# Sensor_IMU_MPU-6000_SPI.net
KiCad netlist of a schematic drawn in EAGLE
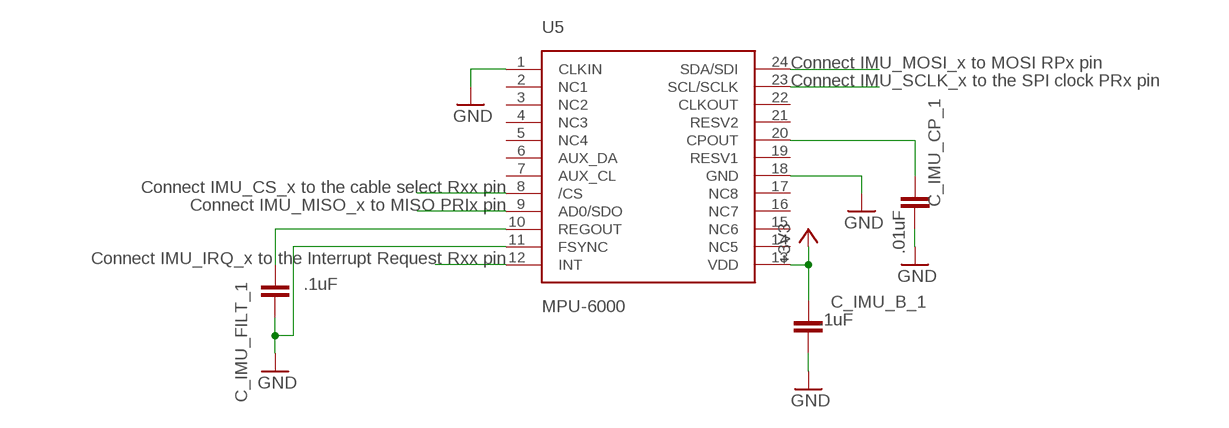
[diagram p0: schematic, sheet 1]

(export (version "E")
  (design (tool "Eeschema 10.0.6"))
  (components
    (comp (ref "C_IMU_B_1")
      (value ".1uF")
      (footprint "eagle-import:0402-CAP")
      (libsource (lib "eagle-import") (part "CAP0402-CAP"))
    )
    (comp (ref "C_IMU_CP_1")
      (value ".01uF")
      (footprint "eagle-import:0402-CAP")
      (libsource (lib "eagle-import") (part "CAP0402-CAP"))
    )
    (comp (ref "C_IMU_FILT_1")
      (value ".1uF")
      (footprint "eagle-import:0402-CAP")
      (libsource (lib "eagle-import") (part "CAP0402-CAP"))
    )
    (comp (ref "U5")
      (value "MPU-6000")
      (footprint "eagle-import:QFN-24")
      (libsource (lib "eagle-import") (part "MPU-3000"))
    )
  )
  (nets
    (net (code "1") (name "+3V3") (class "Default")
      (node (ref "C_IMU_B_1") (pin "2") (pinfunction "2_2") (pintype "passive"))
      (node (ref "U5") (pin "13") (pinfunction "VDD_13") (pintype "bidirectional"))
    )
    (net (code "2") (name "GND") (class "Default")
      (node (ref "C_IMU_B_1") (pin "1") (pinfunction "1_1") (pintype "passive"))
      (node (ref "C_IMU_CP_1") (pin "1") (pinfunction "1_1") (pintype "passive"))
      (node (ref "C_IMU_FILT_1") (pin "1") (pinfunction "1_1") (pintype "passive"))
      (node (ref "U5") (pin "1") (pinfunction "CLKIN_1") (pintype "bidirectional"))
      (node (ref "U5") (pin "11") (pinfunction "FSYNC_11") (pintype "bidirectional"))
      (node (ref "U5") (pin "18") (pinfunction "GND_18") (pintype "bidirectional"))
    )
    (net (code "3") (name "Net-(U5-CPOUT)") (class "Default")
      (node (ref "C_IMU_CP_1") (pin "2") (pinfunction "2_2") (pintype "passive"))
      (node (ref "U5") (pin "20") (pinfunction "CPOUT_20") (pintype "bidirectional"))
    )
    (net (code "4") (name "Net-(U5-REGOUT)") (class "Default")
      (node (ref "C_IMU_FILT_1") (pin "2") (pinfunction "2_2") (pintype "passive"))
      (node (ref "U5") (pin "10") (pinfunction "REGOUT_10") (pintype "bidirectional"))
    )
    (net (code "5") (name "unconnected-(U5-AD0{slash}SDO-Pad9)") (class "Default")
      (node (ref "U5") (pin "9") (pinfunction "AD0/SDO_9") (pintype "bidirectional"))
    )
    (net (code "6") (name "unconnected-(U5-AUX_CL-Pad7)") (class "Default")
      (node (ref "U5") (pin "7") (pinfunction "AUX_CL_7") (pintype "bidirectional"))
    )
    (net (code "7") (name "unconnected-(U5-AUX_DA-Pad6)") (class "Default")
      (node (ref "U5") (pin "6") (pinfunction "AUX_DA_6") (pintype "bidirectional"))
    )
    (net (code "8") (name "unconnected-(U5-CLKOUT-Pad22)") (class "Default")
      (node (ref "U5") (pin "22") (pinfunction "CLKOUT_22") (pintype "bidirectional"))
    )
    (net (code "9") (name "unconnected-(U5-INT-Pad12)") (class "Default")
      (node (ref "U5") (pin "12") (pinfunction "INT_12") (pintype "bidirectional"))
    )
    (net (code "10") (name "unconnected-(U5-NC1-Pad2)") (class "Default")
      (node (ref "U5") (pin "2") (pinfunction "NC1_2") (pintype "bidirectional"))
    )
    (net (code "11") (name "unconnected-(U5-NC2-Pad3)") (class "Default")
      (node (ref "U5") (pin "3") (pinfunction "NC2_3") (pintype "bidirectional"))
    )
    (net (code "12") (name "unconnected-(U5-NC3-Pad4)") (class "Default")
      (node (ref "U5") (pin "4") (pinfunction "NC3_4") (pintype "bidirectional"))
    )
    (net (code "13") (name "unconnected-(U5-NC4-Pad5)") (class "Default")
      (node (ref "U5") (pin "5") (pinfunction "NC4_5") (pintype "bidirectional"))
    )
    (net (code "14") (name "unconnected-(U5-NC5-Pad14)") (class "Default")
      (node (ref "U5") (pin "14") (pinfunction "NC5_14") (pintype "bidirectional"))
    )
    (net (code "15") (name "unconnected-(U5-NC6-Pad15)") (class "Default")
      (node (ref "U5") (pin "15") (pinfunction "NC6_15") (pintype "bidirectional"))
    )
    (net (code "16") (name "unconnected-(U5-NC7-Pad16)") (class "Default")
      (node (ref "U5") (pin "16") (pinfunction "NC7_16") (pintype "bidirectional"))
    )
    (net (code "17") (name "unconnected-(U5-NC8-Pad17)") (class "Default")
      (node (ref "U5") (pin "17") (pinfunction "NC8_17") (pintype "bidirectional"))
    )
    (net (code "18") (name "unconnected-(U5-RESV1-Pad19)") (class "Default")
      (node (ref "U5") (pin "19") (pinfunction "RESV1_19") (pintype "bidirectional"))
    )
    (net (code "19") (name "unconnected-(U5-RESV2-Pad21)") (class "Default")
      (node (ref "U5") (pin "21") (pinfunction "RESV2_21") (pintype "bidirectional"))
    )
    (net (code "20") (name "unconnected-(U5-SCL{slash}SCLK-Pad23)") (class "Default")
      (node (ref "U5") (pin "23") (pinfunction "SCL/SCLK_23") (pintype "bidirectional"))
    )
    (net (code "21") (name "unconnected-(U5-SDA{slash}SDI-Pad24)") (class "Default")
      (node (ref "U5") (pin "24") (pinfunction "SDA/SDI_24") (pintype "bidirectional"))
    )
    (net (code "22") (name "unconnected-(U5-{slash}CS-Pad8)") (class "Default")
      (node (ref "U5") (pin "8") (pinfunction "/CS_8") (pintype "bidirectional"))
    )
  )
)
